# MC34063_Boost.net
KiCad netlist of a schematic drawn in EAGLE
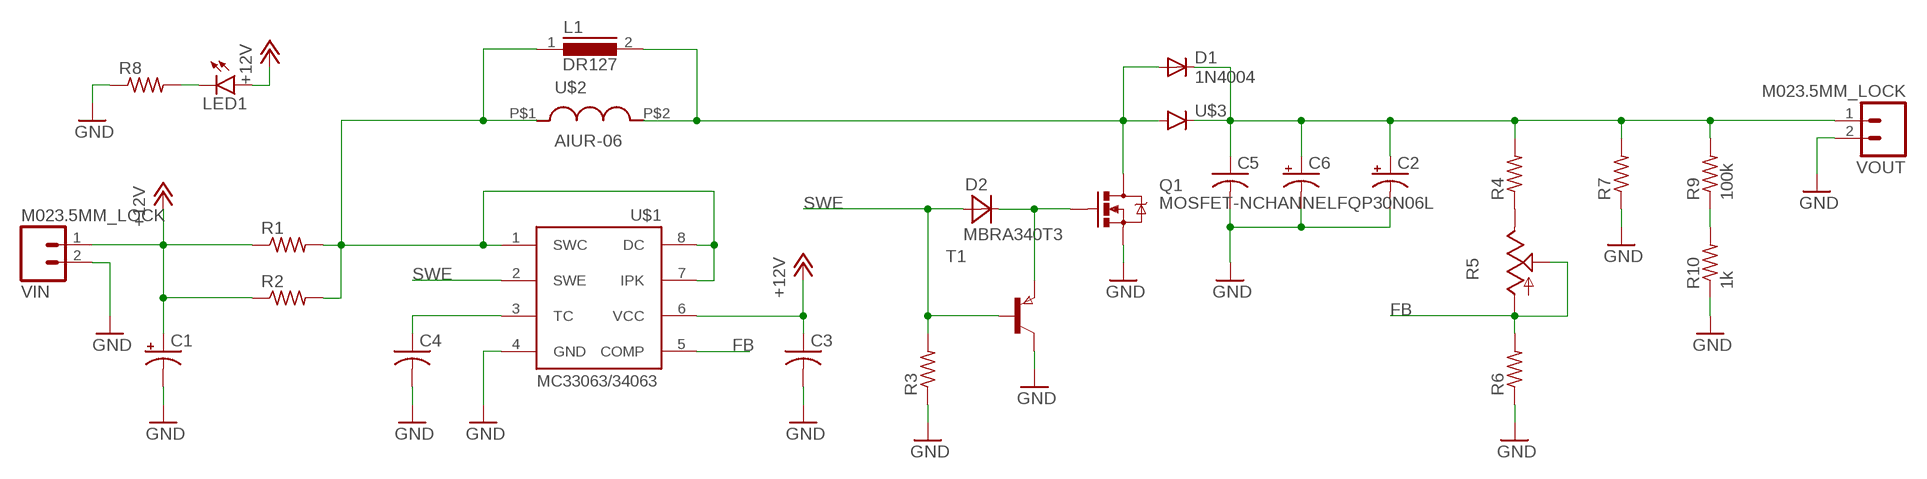
[diagram p0: schematic, sheet 1]

(export (version "E")
  (design (tool "Eeschema 10.0.6"))
  (components
    (comp (ref "C1")
      (value "CPOL-USE3.5-8")
      (footprint "eagle-import:E3,5-8")
      (libsource (lib "eagle-import") (part "CPOL-USE3.5-8"))
    )
    (comp (ref "C2")
      (value "CPOL-USE2.5-6")
      (footprint "eagle-import:E2,5-6")
      (libsource (lib "eagle-import") (part "CPOL-USE2.5-6"))
    )
    (comp (ref "C3")
      (value "C-USC0805K")
      (footprint "eagle-import:C0805K")
      (libsource (lib "eagle-import") (part "C-USC0805K"))
    )
    (comp (ref "C4")
      (value "C-USC0805")
      (footprint "eagle-import:C0805")
      (libsource (lib "eagle-import") (part "C-USC0805"))
    )
    (comp (ref "C5")
      (value "C-USC1206")
      (footprint "eagle-import:C1206")
      (libsource (lib "eagle-import") (part "C-USC1206"))
    )
    (comp (ref "C6")
      (value "CPOL-USE3.5-8")
      (footprint "eagle-import:E3,5-8")
      (libsource (lib "eagle-import") (part "CPOL-USE3.5-8"))
    )
    (comp (ref "D1")
      (value "1N4004")
      (footprint "eagle-import:DO41-10")
      (libsource (lib "eagle-import") (part "1N4004"))
    )
    (comp (ref "D2")
      (value "MBRA340T3")
      (footprint "eagle-import:SMA")
      (libsource (lib "eagle-import") (part "MBRA340T3"))
    )
    (comp (ref "L1")
      (value "DR127")
      (footprint "eagle-import:DR127")
      (libsource (lib "eagle-import") (part "DR127"))
    )
    (comp (ref "LED1")
      (value "LED1206")
      (footprint "eagle-import:LED-1206")
      (libsource (lib "eagle-import") (part "LED1206"))
    )
    (comp (ref "Q1")
      (value "MOSFET-NCHANNELFQP30N06L")
      (footprint "eagle-import:TO220V")
      (libsource (lib "eagle-import") (part "MOSFET-NCHANNELFQP30N06L"))
    )
    (comp (ref "R1")
      (value "R-US_R1206")
      (footprint "eagle-import:R1206")
      (libsource (lib "eagle-import") (part "R-US_R1206"))
    )
    (comp (ref "R2")
      (value "R-US_R1206")
      (footprint "eagle-import:R1206")
      (libsource (lib "eagle-import") (part "R-US_R1206"))
    )
    (comp (ref "R3")
      (value "R-US_R0805")
      (footprint "eagle-import:R0805")
      (libsource (lib "eagle-import") (part "R-US_R0805"))
    )
    (comp (ref "R4")
      (value "R-US_R0805")
      (footprint "eagle-import:R0805")
      (libsource (lib "eagle-import") (part "R-US_R0805"))
    )
    (comp (ref "R5")
      (value "TRIM_US-S64W")
      (footprint "eagle-import:S64W")
      (libsource (lib "eagle-import") (part "TRIM_US-S64W"))
    )
    (comp (ref "R6")
      (value "R-US_R0805")
      (footprint "eagle-import:R0805")
      (libsource (lib "eagle-import") (part "R-US_R0805"))
    )
    (comp (ref "R7")
      (value "R-US_R0805")
      (footprint "eagle-import:R0805")
      (libsource (lib "eagle-import") (part "R-US_R0805"))
    )
    (comp (ref "R8")
      (value "R-US_R0805")
      (footprint "eagle-import:R0805")
      (libsource (lib "eagle-import") (part "R-US_R0805"))
    )
    (comp (ref "R9")
      (value "100k")
      (footprint "eagle-import:R0805")
      (libsource (lib "eagle-import") (part "R-US_R0805"))
    )
    (comp (ref "R10")
      (value "1k")
      (footprint "eagle-import:R0805")
      (libsource (lib "eagle-import") (part "R-US_R0805"))
    )
    (comp (ref "T1")
      (value "PNPSOT223")
      (footprint "eagle-import:SOT223")
      (fields (field (name "MPN") "DJT4030P-13"))
      (libsource (lib "eagle-import") (part "PNPSOT223"))
    )
    (comp (ref "U$1")
      (value "MC33063/MC34063D")
      (footprint "eagle-import:SO08")
      (libsource (lib "eagle-import") (part "MC33063/MC34063D"))
    )
    (comp (ref "U$2")
      (value "AIUR-06")
      (footprint "eagle-import:7MM_LEADS_12MM")
      (libsource (lib "eagle-import") (part "AIUR-06"))
    )
    (comp (ref "U$3")
      (value "DIODESMA")
      (footprint "eagle-import:SMA-DIODE")
      (libsource (lib "eagle-import") (part "DIODESMA"))
    )
    (comp (ref "VIN")
      (value "M023.5MM_LOCK")
      (footprint "eagle-import:SCREWTERMINAL-3.5MM-2_LOCK")
      (libsource (lib "eagle-import") (part "M023.5MM_LOCK"))
    )
    (comp (ref "VOUT")
      (value "M023.5MM_LOCK")
      (footprint "eagle-import:SCREWTERMINAL-3.5MM-2_LOCK")
      (libsource (lib "eagle-import") (part "M023.5MM_LOCK"))
    )
  )
  (nets
    (net (code "1") (name "+12V") (class "Default")
      (node (ref "C1") (pin "+") (pinfunction "+_+") (pintype "passive"))
      (node (ref "C3") (pin "1") (pinfunction "1_1") (pintype "passive"))
      (node (ref "LED1") (pin "A") (pinfunction "A_A") (pintype "passive"))
      (node (ref "R1") (pin "1") (pinfunction "1_1") (pintype "passive"))
      (node (ref "R2") (pin "1") (pinfunction "1_1") (pintype "passive"))
      (node (ref "U$1") (pin "6") (pinfunction "VCC_6") (pintype "power_in"))
      (node (ref "VIN") (pin "1") (pinfunction "1_1") (pintype "passive"))
    )
    (net (code "2") (name "/FB") (class "Default")
      (node (ref "R5") (pin "A") (pinfunction "A_A") (pintype "passive"))
      (node (ref "R5") (pin "S") (pinfunction "S_S") (pintype "passive"))
      (node (ref "R6") (pin "2") (pinfunction "2_2") (pintype "passive"))
      (node (ref "U$1") (pin "5") (pinfunction "COMP_5") (pintype "input"))
    )
    (net (code "3") (name "/SWE") (class "Default")
      (node (ref "D2") (pin "A") (pinfunction "A_A") (pintype "passive"))
      (node (ref "R3") (pin "2") (pinfunction "2_2") (pintype "passive"))
      (node (ref "T1") (pin "1") (pinfunction "B_1") (pintype "passive"))
      (node (ref "U$1") (pin "2") (pinfunction "SWE_2") (pintype "input"))
    )
    (net (code "4") (name "GND") (class "Default")
      (node (ref "C1") (pin "-") (pinfunction "-_-") (pintype "passive"))
      (node (ref "C2") (pin "-") (pinfunction "-_-") (pintype "passive"))
      (node (ref "C3") (pin "2") (pinfunction "2_2") (pintype "passive"))
      (node (ref "C4") (pin "2") (pinfunction "2_2") (pintype "passive"))
      (node (ref "C5") (pin "2") (pinfunction "2_2") (pintype "passive"))
      (node (ref "C6") (pin "-") (pinfunction "-_-") (pintype "passive"))
      (node (ref "Q1") (pin "3") (pinfunction "S_3") (pintype "passive"))
      (node (ref "R10") (pin "1") (pinfunction "1_1") (pintype "passive"))
      (node (ref "R3") (pin "1") (pinfunction "1_1") (pintype "passive"))
      (node (ref "R6") (pin "1") (pinfunction "1_1") (pintype "passive"))
      (node (ref "R7") (pin "1") (pinfunction "1_1") (pintype "passive"))
      (node (ref "R8") (pin "1") (pinfunction "1_1") (pintype "passive"))
      (node (ref "T1") (pin "2") (pinfunction "C_2") (pintype "passive"))
      (node (ref "T1") (pin "4") (pinfunction "C_4") (pintype "passive"))
      (node (ref "U$1") (pin "4") (pinfunction "GND_4") (pintype "power_in"))
      (node (ref "VIN") (pin "2") (pinfunction "2_2") (pintype "passive"))
      (node (ref "VOUT") (pin "2") (pinfunction "2_2") (pintype "passive"))
    )
    (net (code "5") (name "Net-(C2-Pad+)") (class "Default")
      (node (ref "C2") (pin "+") (pinfunction "+_+") (pintype "passive"))
      (node (ref "C5") (pin "1") (pinfunction "1_1") (pintype "passive"))
      (node (ref "C6") (pin "+") (pinfunction "+_+") (pintype "passive"))
      (node (ref "D1") (pin "C") (pinfunction "C_C") (pintype "passive"))
      (node (ref "R4") (pin "2") (pinfunction "2_2") (pintype "passive"))
      (node (ref "R7") (pin "2") (pinfunction "2_2") (pintype "passive"))
      (node (ref "R9") (pin "2") (pinfunction "2_2") (pintype "passive"))
      (node (ref "U$3") (pin "C") (pinfunction "C_C") (pintype "passive"))
      (node (ref "VOUT") (pin "1") (pinfunction "1_1") (pintype "passive"))
    )
    (net (code "6") (name "Net-(LED1-PadC)") (class "Default")
      (node (ref "LED1") (pin "C") (pinfunction "C_C") (pintype "passive"))
      (node (ref "R8") (pin "2") (pinfunction "2_2") (pintype "passive"))
    )
    (net (code "7") (name "Net-(Q1-D)") (class "Default")
      (node (ref "D1") (pin "A") (pinfunction "A_A") (pintype "passive"))
      (node (ref "L1") (pin "2") (pinfunction "2_2") (pintype "passive"))
      (node (ref "Q1") (pin "2") (pinfunction "D_2") (pintype "passive"))
      (node (ref "U$2") (pin "P$2") (pinfunction "2_P$2") (pintype "bidirectional"))
      (node (ref "U$3") (pin "A") (pinfunction "A_A") (pintype "passive"))
    )
    (net (code "8") (name "Net-(Q1-G)") (class "Default")
      (node (ref "D2") (pin "C") (pinfunction "C_C") (pintype "passive"))
      (node (ref "Q1") (pin "1") (pinfunction "G_1") (pintype "passive"))
      (node (ref "T1") (pin "3") (pinfunction "E_3") (pintype "passive"))
    )
    (net (code "9") (name "Net-(R4-Pad1)") (class "Default")
      (node (ref "R4") (pin "1") (pinfunction "1_1") (pintype "passive"))
      (node (ref "R5") (pin "E") (pinfunction "E_E") (pintype "passive"))
    )
    (net (code "10") (name "Net-(R10-Pad2)") (class "Default")
      (node (ref "R10") (pin "2") (pinfunction "2_2") (pintype "passive"))
      (node (ref "R9") (pin "1") (pinfunction "1_1") (pintype "passive"))
    )
    (net (code "11") (name "Net-(U$1-DC)") (class "Default")
      (node (ref "L1") (pin "1") (pinfunction "1_1") (pintype "passive"))
      (node (ref "R1") (pin "2") (pinfunction "2_2") (pintype "passive"))
      (node (ref "R2") (pin "2") (pinfunction "2_2") (pintype "passive"))
      (node (ref "U$1") (pin "1") (pinfunction "SWC_1") (pintype "input"))
      (node (ref "U$1") (pin "7") (pinfunction "IPK_7") (pintype "bidirectional"))
      (node (ref "U$1") (pin "8") (pinfunction "DC_8") (pintype "input"))
      (node (ref "U$2") (pin "P$1") (pinfunction "1_P$1") (pintype "bidirectional"))
    )
    (net (code "12") (name "Net-(U$1-TC)") (class "Default")
      (node (ref "C4") (pin "1") (pinfunction "1_1") (pintype "passive"))
      (node (ref "U$1") (pin "3") (pinfunction "TC_3") (pintype "input"))
    )
  )
)
